# Alert_Button.net
KiCad netlist of a schematic drawn in Altium Designer
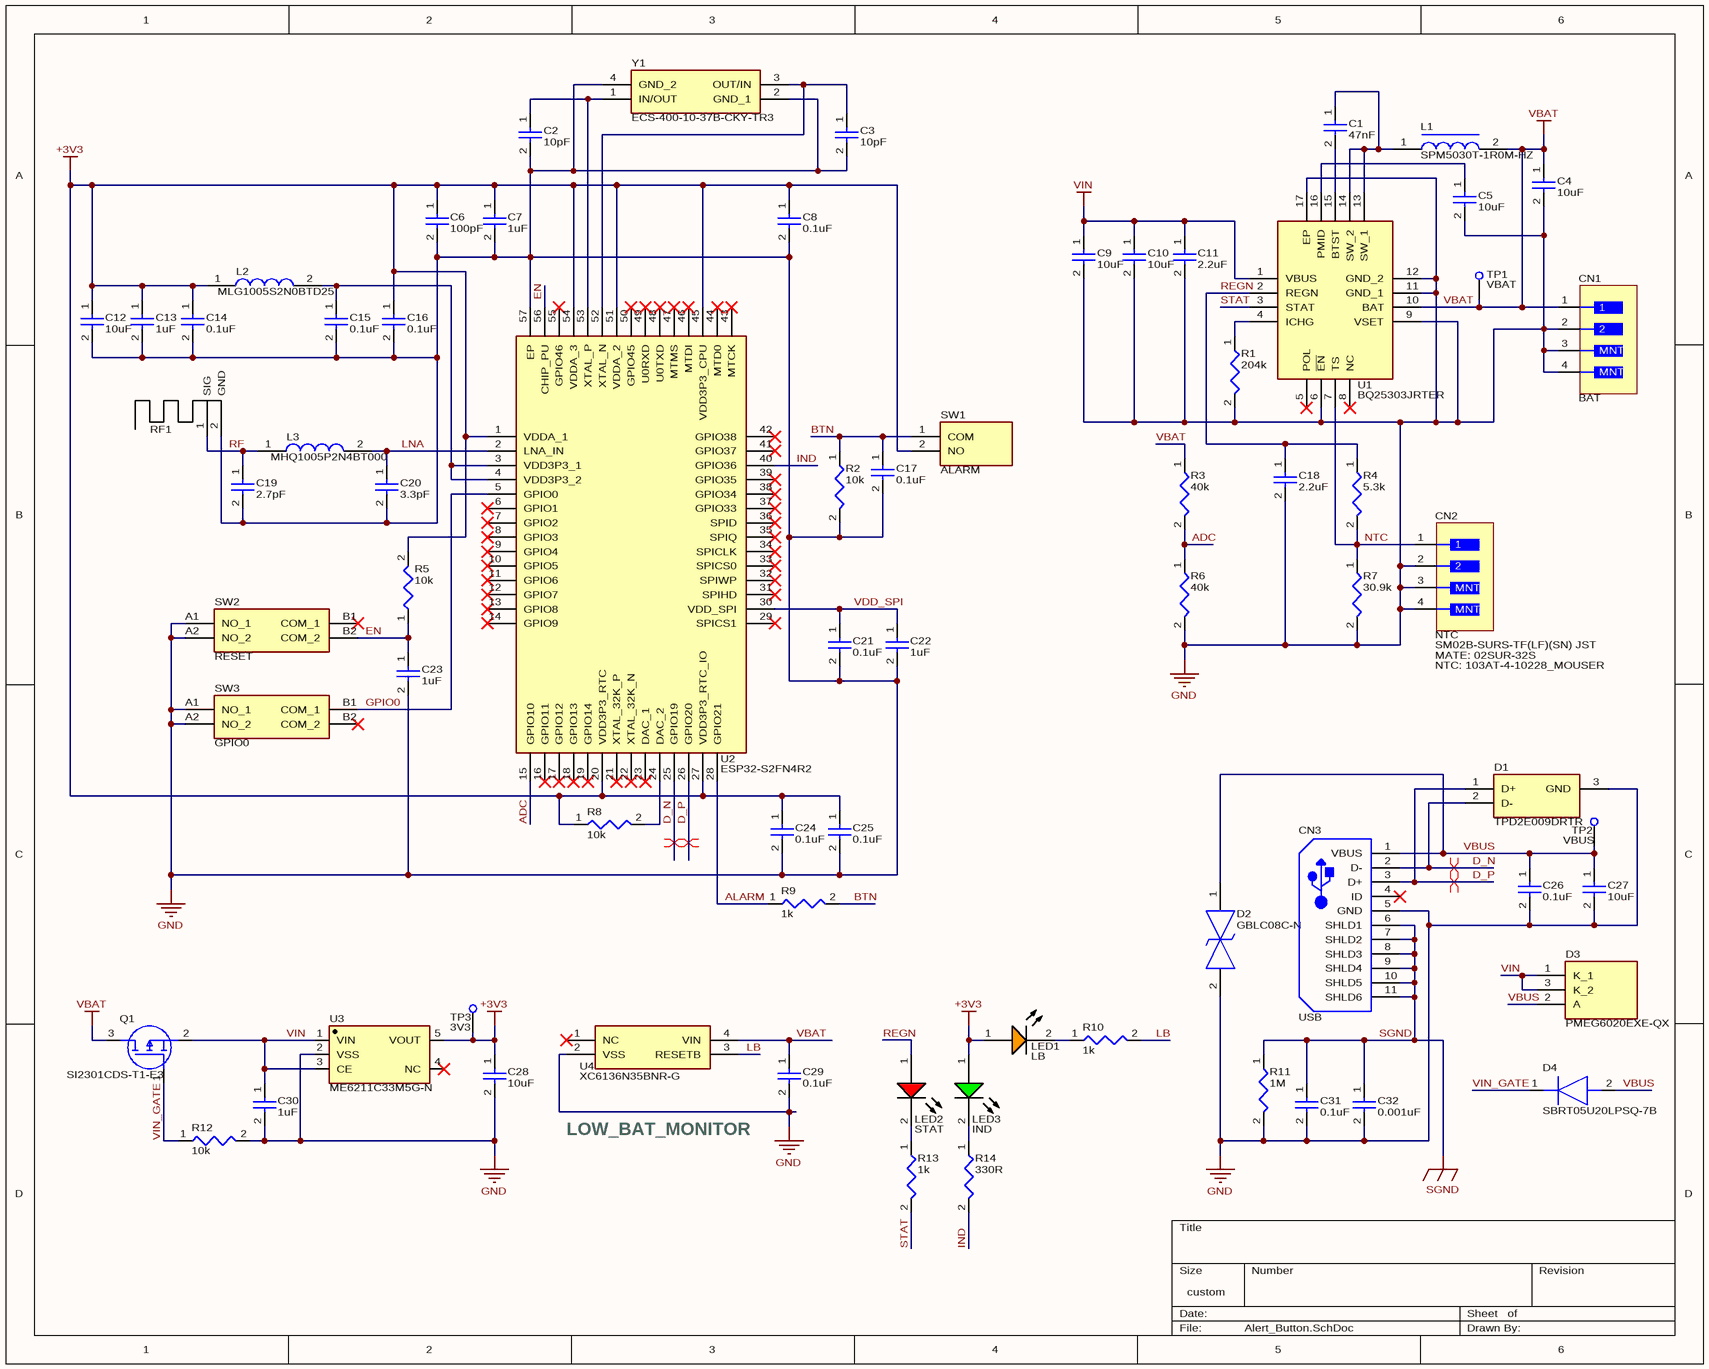
[diagram p0: Alert_Button.SchDoc]

(export (version "E")
  (design (tool "Eeschema 10.0.6"))
  (components
    (comp (ref "C1")
      (value "47nF")
      (footprint "SamacSys:CAPC1005X55N")
      (description "C0402")
      (libsource (lib "SamacSys") (part "C0402"))
    )
    (comp (ref "C2")
      (value "10pF")
      (footprint "SamacSys:CAPC1005X55N")
      (description "C0402")
      (libsource (lib "SamacSys") (part "C0402"))
    )
    (comp (ref "C3")
      (value "10pF")
      (footprint "SamacSys:CAPC1005X55N")
      (description "C0402")
      (libsource (lib "SamacSys") (part "C0402"))
    )
    (comp (ref "C4")
      (value "10uF")
      (footprint "SamacSys:CAPC1608X90N")
      (description "C0603")
      (libsource (lib "SamacSys") (part "C0603"))
    )
    (comp (ref "C5")
      (value "10uF")
      (footprint "SamacSys:CAPC1608X90N")
      (description "C0603")
      (libsource (lib "SamacSys") (part "C0603"))
    )
    (comp (ref "C6")
      (value "100pF")
      (footprint "SamacSys:CAPC1005X55N")
      (description "C0402")
      (libsource (lib "SamacSys") (part "C0402"))
    )
    (comp (ref "C7")
      (value "1uF")
      (footprint "SamacSys:CAPC1005X55N")
      (description "C0402")
      (libsource (lib "SamacSys") (part "C0402"))
    )
    (comp (ref "C8")
      (value "0.1uF")
      (footprint "SamacSys:CAPC1005X55N")
      (description "C0402")
      (libsource (lib "SamacSys") (part "C0402"))
    )
    (comp (ref "C9")
      (value "10uF")
      (footprint "SamacSys:CAPC1608X90N")
      (description "C0603")
      (libsource (lib "SamacSys") (part "C0603"))
    )
    (comp (ref "C10")
      (value "10uF")
      (footprint "SamacSys:CAPC1608X90N")
      (description "C0603")
      (libsource (lib "SamacSys") (part "C0603"))
    )
    (comp (ref "C11")
      (value "2.2uF")
      (footprint "SamacSys:CAPC1005X55N")
      (description "C0402")
      (libsource (lib "SamacSys") (part "C0402"))
    )
    (comp (ref "C12")
      (value "10uF")
      (footprint "SamacSys:CAPC2012X140N")
      (description "C0805")
      (libsource (lib "SamacSys") (part "C0805"))
    )
    (comp (ref "C13")
      (value "1uF")
      (footprint "SamacSys:CAPC1005X55N")
      (description "C0402")
      (libsource (lib "SamacSys") (part "C0402"))
    )
    (comp (ref "C14")
      (value "0.1uF")
      (footprint "SamacSys:CAPC1005X55N")
      (description "C0402")
      (libsource (lib "SamacSys") (part "C0402"))
    )
    (comp (ref "C15")
      (value "0.1uF")
      (footprint "SamacSys:CAPC1005X55N")
      (description "C0402")
      (libsource (lib "SamacSys") (part "C0402"))
    )
    (comp (ref "C16")
      (value "0.1uF")
      (footprint "SamacSys:CAPC1005X55N")
      (description "C0402")
      (libsource (lib "SamacSys") (part "C0402"))
    )
    (comp (ref "C17")
      (value "0.1uF")
      (footprint "SamacSys:CAPC1005X55N")
      (description "C0402")
      (libsource (lib "SamacSys") (part "C0402"))
    )
    (comp (ref "C18")
      (value "2.2uF")
      (footprint "SamacSys:CAPC1005X55N")
      (description "C0402")
      (libsource (lib "SamacSys") (part "C0402"))
    )
    (comp (ref "C19")
      (value "2.7pF")
      (footprint "SamacSys:CAPC1005X56N")
      (description "C0402")
      (fields
        (field (name "MANUFACTURER_PART_NUMBER") "04023U2R7BAT2A")
        (field (name "MOUSER PART NUMBER") "581-04023U2.7B")
      )
      (libsource (lib "SamacSys") (part "04023U2R7BAT2A"))
    )
    (comp (ref "C20")
      (value "3.3pF")
      (footprint "SamacSys:CAPC1005X56N")
      (description "C0402")
      (fields (field (name "MANUFACTURER_PART_NUMBER") "04023A3R3CAT2A"))
      (libsource (lib "SamacSys") (part "04023A3R3CAT2A"))
    )
    (comp (ref "C21")
      (value "0.1uF")
      (footprint "SamacSys:CAPC1005X55N")
      (description "C0402")
      (libsource (lib "SamacSys") (part "C0402"))
    )
    (comp (ref "C22")
      (value "1uF")
      (footprint "SamacSys:CAPC1005X55N")
      (description "C0402")
      (libsource (lib "SamacSys") (part "C0402"))
    )
    (comp (ref "C23")
      (value "1uF")
      (footprint "SamacSys:CAPC1005X55N")
      (description "C0402")
      (libsource (lib "SamacSys") (part "C0402"))
    )
    (comp (ref "C24")
      (value "0.1uF")
      (footprint "SamacSys:CAPC1005X55N")
      (description "C0402")
      (libsource (lib "SamacSys") (part "C0402"))
    )
    (comp (ref "C25")
      (value "0.1uF")
      (footprint "SamacSys:CAPC1005X55N")
      (description "C0402")
      (libsource (lib "SamacSys") (part "C0402"))
    )
    (comp (ref "C26")
      (value "0.1uF")
      (footprint "SamacSys:CAPC1005X55N")
      (description "C0402")
      (libsource (lib "SamacSys") (part "C0402"))
    )
    (comp (ref "C27")
      (value "10uF")
      (footprint "SamacSys:CAPC1608X90N")
      (description "C0603")
      (libsource (lib "SamacSys") (part "C0603"))
    )
    (comp (ref "C28")
      (value "10uF")
      (footprint "SamacSys:CAPC1608X90N")
      (description "C0603")
      (libsource (lib "SamacSys") (part "C0603"))
    )
    (comp (ref "C29")
      (value "0.1uF")
      (footprint "SamacSys:CAPC1005X55N")
      (description "C0402")
      (libsource (lib "") (part "C0402_1"))
    )
    (comp (ref "C30")
      (value "1uF")
      (footprint "SamacSys:CAPC1005X55N")
      (description "C0402")
      (libsource (lib "SamacSys") (part "C0402"))
    )
    (comp (ref "C31")
      (value "0.1uF")
      (footprint "SamacSys:CAPC1005X55N")
      (description "C0402")
      (libsource (lib "SamacSys") (part "C0402"))
    )
    (comp (ref "C32")
      (value "0.001uF")
      (footprint "SamacSys:CAPC1005X55N")
      (description "C0402")
      (libsource (lib "SamacSys") (part "C0402"))
    )
    (comp (ref "CN1")
      (value "BAT")
      (footprint "SM02B-SURS-TF(LF)(SN)")
      (description "Connector")
      (fields
        (field (name "MANUFACTURER_PART_NUMBER") "SM02B-SURS-TF(LF)(SN)")
        (field (name "MOUSER PART NUMBER") "306-SM02B-SURS-TF(LF)(SN)")
      )
      (libsource (lib "Schlib1") (part "SM02B-SURS-TF(LF)(SN)"))
    )
    (comp (ref "CN2")
      (value "NTC")
      (footprint "SM02B-SURS-TF(LF)(SN)")
      (description "Connector")
      (fields
        (field (name "MANUFACTURER_PART_NUMBER") "SM02B-SURS-TF(LF)(SN)")
        (field (name "MOUSER PART NUMBER") "306-SM02B-SURS-TF(LF)(SN)")
      )
      (libsource (lib "Schlib1") (part "SM02B-SURS-TF(LF)(SN)"))
    )
    (comp (ref "CN3")
      (value "USB")
      (footprint "105017-0001")
      (description "Micro USB Connector")
      (fields
        (field (name "MANUFACTURER_PART_NUMBER") "105017-0001")
        (field (name "MOUSER PART NUMBER") "538-105017-0001")
      )
      (libsource (lib "SamacSys") (part "105017-0001"))
    )
    (comp (ref "D1")
      (value "TPD2E009DRTR")
      (footprint "SamacSys:SOTFL35P100X50-3N")
      (description "Integrated Circuit")
      (fields (field (name "MOUSER PART NUMBER") "595-TPD2E009DRTR"))
      (libsource (lib "SamacSys") (part "TPD2E009DRTR"))
    )
    (comp (ref "D2")
      (value "GBLC08C-N")
      (footprint "SOD-323_L1.8-W1.3-LS2.5-BI")
      (description "ESD DIODE-BI_LCSC#C314256")
      (libsource (lib "Schlib1") (part "GBLC08C-N"))
    )
    (comp (ref "D3")
      (value "PMEG6020EXE-QX")
      (footprint "SamacSys:PMEG6020EXEQX")
      (description "Schottky Diode")
      (libsource (lib "SamacSys") (part "PMEG6020EXE-QX"))
    )
    (comp (ref "D4")
      (value "SBRT05U20LPSQ-7B")
      (footprint "SamacSys:SBRT05U20LPSQ7B")
      (description "Diode")
      (fields (field (name "MOUSER PART NUMBER") "621-SBRT05U20LPSQ-7B"))
      (libsource (lib "SamacSys") (part "SBRT05U20LPSQ-7B"))
    )
    (comp (ref "L1")
      (value "SPM5030T-1R0M-HZ")
      (footprint "SamacSys:SPM5030")
      (description "Inductor (FeSi Core)")
      (fields (field (name "MOUSER PART NUMBER") "810-SPM5030T-1R0M-HZ"))
      (libsource (lib "SamacSys") (part "SPM5030T-1R0M-HZ"))
    )
    (comp (ref "L2")
      (value "MLG1005S2N0BTD25")
      (footprint "SamacSys:MLG1005")
      (description "Inductor")
      (fields (field (name "MOUSER PART NUMBER") "810-MLG1005S2N0BTD25"))
      (libsource (lib "SamacSys") (part "MLG1005S2N0BTD25"))
    )
    (comp (ref "L3")
      (value "MHQ1005P2N4BT000")
      (footprint "SamacSys:MHQ1005")
      (description "Inductor")
      (libsource (lib "SamacSys") (part "MHQ1005P2N4BT000"))
    )
    (comp (ref "LED1")
      (value "LB")
      (footprint "SM0402OC")
      (description "LED ORANGE")
      (fields
        (field (name "MANUFACTURER_PART_NUMBER") "SM0402OC")
        (field (name "MOUSER PART NUMBER") "749-SM0402OC")
      )
      (libsource (lib "SamacSys") (part "SM0402OC"))
    )
    (comp (ref "LED2")
      (value "STAT")
      (footprint "SamacSys:SM0402RC")
      (description "LED RED")
      (fields
        (field (name "MANUFACTURER_PART_NUMBER") "SM0402RC")
        (field (name "MOUSER PART NUMBER") "749-SM0402RC")
      )
      (libsource (lib "SamacSys") (part "SM0402RC"))
    )
    (comp (ref "LED3")
      (value "IND")
      (footprint "SamacSys:SM0402GC")
      (description "LED GREEN")
      (fields
        (field (name "MANUFACTURER_PART_NUMBER") "SM0402GC")
        (field (name "MOUSER PART NUMBER") "749-SM0402GC")
      )
      (libsource (lib "SamacSys") (part "SM0402GC"))
    )
    (comp (ref "Q1")
      (value "SI2301CDS-T1-E3")
      (footprint "SamacSys:SOT95P237X112-3N")
      (description "MOSFET (P-Channel)")
      (fields (field (name "MOUSER PART NUMBER") "781-SI2301CDS-E3"))
      (libsource (lib "SamacSys") (part "SI2301CDS-T1-E3"))
    )
    (comp (ref "R1")
      (value "204k")
      (footprint "SamacSys:ERA2AED122X")
      (description "R0402")
      (libsource (lib "SamacSys") (part "R0402"))
    )
    (comp (ref "R2")
      (value "10k")
      (footprint "SamacSys:ERA2AED122X")
      (description "R0402")
      (libsource (lib "SamacSys") (part "R0402"))
    )
    (comp (ref "R3")
      (value "40k")
      (footprint "SamacSys:ERA2AED122X")
      (description "R0402")
      (libsource (lib "SamacSys") (part "R0402"))
    )
    (comp (ref "R4")
      (value "5.3k")
      (footprint "SamacSys:ERA2AED122X")
      (description "R0402")
      (libsource (lib "SamacSys") (part "R0402"))
    )
    (comp (ref "R5")
      (value "10k")
      (footprint "SamacSys:ERA2AED122X")
      (description "R0402")
      (libsource (lib "SamacSys") (part "R0402"))
    )
    (comp (ref "R6")
      (value "40k")
      (footprint "SamacSys:ERA2AED122X")
      (description "R0402")
      (libsource (lib "SamacSys") (part "R0402"))
    )
    (comp (ref "R7")
      (value "30.9k")
      (footprint "SamacSys:ERA2AED122X")
      (description "R0402")
      (libsource (lib "SamacSys") (part "R0402"))
    )
    (comp (ref "R8")
      (value "10k")
      (footprint "SamacSys:ERA2AED122X")
      (description "R0402")
      (libsource (lib "SamacSys") (part "R0402"))
    )
    (comp (ref "R9")
      (value "1k")
      (footprint "SamacSys:ERA2AED122X")
      (description "R0402")
      (libsource (lib "SamacSys") (part "R0402"))
    )
    (comp (ref "R10")
      (value "1k")
      (footprint "SamacSys:ERA2AED122X")
      (description "R0402")
      (libsource (lib "SamacSys") (part "R0402"))
    )
    (comp (ref "R11")
      (value "1M")
      (footprint "SamacSys:ERA2AED122X")
      (description "R0402")
      (libsource (lib "SamacSys") (part "R0402"))
    )
    (comp (ref "R12")
      (value "10k")
      (footprint "SamacSys:ERA2AED122X")
      (description "R0402")
      (libsource (lib "SamacSys") (part "R0402"))
    )
    (comp (ref "R13")
      (value "1k")
      (footprint "SamacSys:ERA2AED122X")
      (description "R0402")
      (libsource (lib "SamacSys") (part "R0402"))
    )
    (comp (ref "R14")
      (value "330R")
      (footprint "SamacSys:ERA2AED122X")
      (description "R0402")
      (libsource (lib "SamacSys") (part "R0402"))
    )
    (comp (ref "RF1") (value "Antenna") (footprint "SWRA117D") (libsource (lib "Schlib1") (part "Antenna")))
    (comp (ref "SW1")
      (value "ALARM")
      (footprint "SamacSys:TS1088R02026")
      (description "Switch")
      (fields (field (name "MANUFACTURER_PART_NUMBER") "TS-1088R-02026"))
      (libsource (lib "SamacSys") (part "TS-1088R-02026"))
    )
    (comp (ref "SW2")
      (value "RESET")
      (footprint "SamacSys:EVPBB0AAB000")
      (description "Switch")
      (fields
        (field (name "MANUFACTURER_PART_NUMBER") "EVP-BB0AAB000")
        (field (name "MOUSER PART NUMBER") "667-EVP-BB0AAB000")
      )
      (libsource (lib "SamacSys") (part "EVP-BB0AAB000"))
    )
    (comp (ref "SW3")
      (value "GPIO0")
      (footprint "SamacSys:EVPBB0AAB000")
      (description "Switch")
      (fields
        (field (name "MANUFACTURER_PART_NUMBER") "EVP-BB0AAB000")
        (field (name "MOUSER PART NUMBER") "667-EVP-BB0AAB000")
      )
      (libsource (lib "SamacSys") (part "EVP-BB0AAB000"))
    )
    (comp (ref "TP1")
      (value "VBAT")
      (footprint "TP")
      (description "TestPoint")
      (libsource (lib "Schlib1") (part "TestPoint"))
    )
    (comp (ref "TP2")
      (value "VBUS")
      (footprint "TP")
      (description "TestPoint")
      (libsource (lib "Schlib1") (part "TestPoint"))
    )
    (comp (ref "TP3")
      (value "3V3")
      (footprint "TP")
      (description "TestPoint")
      (libsource (lib "Schlib1") (part "TestPoint"))
    )
    (comp (ref "U1")
      (value "BQ25303JRTER")
      (footprint "SamacSys:QFN50P300X300X80-17N-D")
      (description "Integrated Circuit")
      (fields (field (name "MOUSER PART NUMBER") "595-BQ25303JRTER"))
      (libsource (lib "*") (part "BQ25303JRTER"))
    )
    (comp (ref "U2")
      (value "ESP32-S2FN4R2")
      (footprint "SamacSys:QFN40P700X700X90-57N-D")
      (description "Integrated Circuit")
      (fields (field (name "MOUSER PART NUMBER") "356-ESP32-S2FN4R2"))
      (libsource (lib "SamacSys") (part "ESP32-S2FN4R2"))
    )
    (comp (ref "U3")
      (value "ME6211C33M5G-N")
      (footprint "SOT95P270X145-5N")
      (description "LCSC +3.3V LDO 500mA VDIF=120mV@100mA")
      (libsource (lib "Schlib1") (part "ME6211C33M5G-N"))
    )
    (comp (ref "U4")
      (value "XC6136N35BNR-G")
      (footprint "SamacSys:XC6136C12ANRG")
      (description "Integrated Circuit")
      (fields (field (name "MOUSER PART NUMBER") "865-XC6136N35BNR-G"))
      (libsource (lib "SamacSys") (part "XC6136N35BNR-G"))
    )
    (comp (ref "Y1")
      (value "ECS-400-10-37B-CKY-TR3")
      (footprint "SamacSys:ECS4001037BCKYTR3")
      (description "Crystal or Oscillator")
      (fields (field (name "MOUSER PART NUMBER") "520-EC4001037BCKYTR3"))
      (libsource (lib "SamacSys") (part "ECS-400-10-37B-CKY-TR3"))
    )
  )
  (nets
    (net (code "1") (name "+3V3") (class "Default")
      (node (ref "C12") (pin "1") (pinfunction "1_1") (pintype "passive"))
      (node (ref "C13") (pin "1") (pinfunction "1_1") (pintype "passive"))
      (node (ref "C14") (pin "1") (pinfunction "1_1") (pintype "passive"))
      (node (ref "C16") (pin "1") (pinfunction "1_1") (pintype "passive"))
      (node (ref "C24") (pin "1") (pinfunction "1_1") (pintype "passive"))
      (node (ref "C25") (pin "1") (pinfunction "1_1") (pintype "passive"))
      (node (ref "C28") (pin "1") (pinfunction "1_1") (pintype "passive"))
      (node (ref "C6") (pin "1") (pinfunction "1_1") (pintype "passive"))
      (node (ref "C7") (pin "1") (pinfunction "1_1") (pintype "passive"))
      (node (ref "C8") (pin "1") (pinfunction "1_1") (pintype "passive"))
      (node (ref "L2") (pin "1") (pinfunction "1_1") (pintype "passive"))
      (node (ref "LED1") (pin "1") (pinfunction "A_1") (pintype "passive"))
      (node (ref "LED3") (pin "1") (pinfunction "A_1") (pintype "passive"))
      (node (ref "R5") (pin "2") (pinfunction "2_2") (pintype "passive"))
      (node (ref "R8") (pin "1") (pinfunction "1_1") (pintype "passive"))
      (node (ref "SW1") (pin "2") (pinfunction "NO_2") (pintype "passive"))
      (node (ref "TP3") (pin "1") (pinfunction "1_1") (pintype "passive"))
      (node (ref "U2") (pin "1") (pinfunction "VDDA_1_1") (pintype "passive"))
      (node (ref "U2") (pin "20") (pinfunction "VDD3P3_RTC_20") (pintype "passive"))
      (node (ref "U2") (pin "27") (pinfunction "VDD3P3_RTC_IO_27") (pintype "passive"))
      (node (ref "U2") (pin "45") (pinfunction "VDD3P3_CPU_45") (pintype "passive"))
      (node (ref "U2") (pin "51") (pinfunction "VDDA_2_51") (pintype "passive"))
      (node (ref "U2") (pin "54") (pinfunction "VDDA_3_54") (pintype "passive"))
      (node (ref "U3") (pin "5") (pinfunction "VOUT_5") (pintype "passive"))
    )
    (net (code "2") (name "/ADC") (class "Default")
      (node (ref "R3") (pin "2") (pinfunction "2_2") (pintype "passive"))
      (node (ref "R6") (pin "1") (pinfunction "1_1") (pintype "passive"))
      (node (ref "U2") (pin "15") (pinfunction "GPIO10_15") (pintype "passive"))
    )
    (net (code "3") (name "/ALARM") (class "Default")
      (node (ref "R9") (pin "1") (pinfunction "1_1") (pintype "passive"))
      (node (ref "U2") (pin "28") (pinfunction "GPIO21_28") (pintype "passive"))
    )
    (net (code "4") (name "/BTN") (class "Default")
      (node (ref "C17") (pin "1") (pinfunction "1_1") (pintype "passive"))
      (node (ref "R2") (pin "1") (pinfunction "1_1") (pintype "passive"))
      (node (ref "R9") (pin "2") (pinfunction "2_2") (pintype "passive"))
      (node (ref "SW1") (pin "1") (pinfunction "COM_1") (pintype "passive"))
    )
    (net (code "5") (name "/D_N") (class "Default")
      (node (ref "CN3") (pin "2") (pinfunction "D-_2") (pintype "passive"))
      (node (ref "D1") (pin "2") (pinfunction "D-_2") (pintype "passive"))
      (node (ref "U2") (pin "25") (pinfunction "GPIO19_25") (pintype "passive"))
    )
    (net (code "6") (name "/D_P") (class "Default")
      (node (ref "CN3") (pin "3") (pinfunction "D+_3") (pintype "passive"))
      (node (ref "D1") (pin "1") (pinfunction "D+_1") (pintype "passive"))
      (node (ref "U2") (pin "26") (pinfunction "GPIO20_26") (pintype "passive"))
    )
    (net (code "7") (name "/EN") (class "Default")
      (node (ref "C23") (pin "1") (pinfunction "1_1") (pintype "passive"))
      (node (ref "R5") (pin "1") (pinfunction "1_1") (pintype "passive"))
      (node (ref "SW2") (pin "B2") (pinfunction "COM_2_B2") (pintype "passive"))
      (node (ref "U2") (pin "56") (pinfunction "CHIP_PU_56") (pintype "passive"))
    )
    (net (code "8") (name "/GPIO0") (class "Default")
      (node (ref "SW3") (pin "B1") (pinfunction "COM_1_B1") (pintype "passive"))
      (node (ref "U2") (pin "5") (pinfunction "GPIO0_5") (pintype "passive"))
    )
    (net (code "9") (name "/IND") (class "Default")
      (node (ref "R14") (pin "2") (pinfunction "2_2") (pintype "passive"))
      (node (ref "U2") (pin "40") (pinfunction "GPIO36_40") (pintype "passive"))
    )
    (net (code "10") (name "/LB") (class "Default")
      (node (ref "R10") (pin "2") (pinfunction "2_2") (pintype "passive"))
      (node (ref "U4") (pin "3") (pinfunction "RESETB_3") (pintype "passive"))
    )
    (net (code "11") (name "/LNA") (class "Default")
      (node (ref "C20") (pin "1") (pinfunction "1_1") (pintype "passive"))
      (node (ref "L3") (pin "2") (pinfunction "2_2") (pintype "passive"))
      (node (ref "U2") (pin "2") (pinfunction "LNA_IN_2") (pintype "passive"))
    )
    (net (code "12") (name "/NTC") (class "Default")
      (node (ref "CN2") (pin "1") (pinfunction "1_1") (pintype "passive"))
      (node (ref "R4") (pin "2") (pinfunction "2_2") (pintype "passive"))
      (node (ref "R7") (pin "1") (pinfunction "1_1") (pintype "passive"))
      (node (ref "U1") (pin "7") (pinfunction "TS_7") (pintype "passive"))
    )
    (net (code "13") (name "/REGN") (class "Default")
      (node (ref "C18") (pin "1") (pinfunction "1_1") (pintype "passive"))
      (node (ref "LED2") (pin "1") (pinfunction "A_1") (pintype "passive"))
      (node (ref "R4") (pin "1") (pinfunction "1_1") (pintype "passive"))
      (node (ref "U1") (pin "2") (pinfunction "REGN_2") (pintype "passive"))
    )
    (net (code "14") (name "/RF") (class "Default")
      (node (ref "C19") (pin "1") (pinfunction "1_1") (pintype "passive"))
      (node (ref "L3") (pin "1") (pinfunction "1_1") (pintype "passive"))
      (node (ref "RF1") (pin "1") (pinfunction "SIG_1") (pintype "passive"))
    )
    (net (code "15") (name "/STAT") (class "Default")
      (node (ref "R13") (pin "2") (pinfunction "2_2") (pintype "passive"))
      (node (ref "U1") (pin "3") (pinfunction "STAT_3") (pintype "passive"))
    )
    (net (code "16") (name "/VBUS") (class "Default")
      (node (ref "C26") (pin "1") (pinfunction "1_1") (pintype "passive"))
      (node (ref "C27") (pin "1") (pinfunction "1_1") (pintype "passive"))
      (node (ref "CN3") (pin "1") (pinfunction "VBUS_1") (pintype "passive"))
      (node (ref "D2") (pin "1") (pinfunction "1_1") (pintype "passive"))
      (node (ref "D3") (pin "2") (pinfunction "A_2") (pintype "passive"))
      (node (ref "D4") (pin "2") (pinfunction "A_2") (pintype "passive"))
      (node (ref "TP2") (pin "1") (pinfunction "1_1") (pintype "passive"))
    )
    (net (code "17") (name "/VDD_SPI") (class "Default")
      (node (ref "C21") (pin "1") (pinfunction "1_1") (pintype "passive"))
      (node (ref "C22") (pin "1") (pinfunction "1_1") (pintype "passive"))
      (node (ref "U2") (pin "30") (pinfunction "VDD_SPI_30") (pintype "passive"))
    )
    (net (code "18") (name "/VIN_GATE") (class "Default")
      (node (ref "D4") (pin "1") (pinfunction "K_1") (pintype "passive"))
      (node (ref "Q1") (pin "1") (pinfunction "G_1") (pintype "passive"))
      (node (ref "R12") (pin "1") (pinfunction "1_1") (pintype "passive"))
    )
    (net (code "19") (name "GND") (class "Default")
      (node (ref "C10") (pin "2") (pinfunction "2_2") (pintype "passive"))
      (node (ref "C11") (pin "2") (pinfunction "2_2") (pintype "passive"))
      (node (ref "C12") (pin "2") (pinfunction "2_2") (pintype "passive"))
      (node (ref "C13") (pin "2") (pinfunction "2_2") (pintype "passive"))
      (node (ref "C14") (pin "2") (pinfunction "2_2") (pintype "passive"))
      (node (ref "C15") (pin "2") (pinfunction "2_2") (pintype "passive"))
      (node (ref "C16") (pin "2") (pinfunction "2_2") (pintype "passive"))
      (node (ref "C17") (pin "2") (pinfunction "2_2") (pintype "passive"))
      (node (ref "C18") (pin "2") (pinfunction "2_2") (pintype "passive"))
      (node (ref "C19") (pin "2") (pinfunction "2_2") (pintype "passive"))
      (node (ref "C2") (pin "2") (pinfunction "2_2") (pintype "passive"))
      (node (ref "C20") (pin "2") (pinfunction "2_2") (pintype "passive"))
      (node (ref "C21") (pin "2") (pinfunction "2_2") (pintype "passive"))
      (node (ref "C22") (pin "2") (pinfunction "2_2") (pintype "passive"))
      (node (ref "C23") (pin "2") (pinfunction "2_2") (pintype "passive"))
      (node (ref "C24") (pin "2") (pinfunction "2_2") (pintype "passive"))
      (node (ref "C25") (pin "2") (pinfunction "2_2") (pintype "passive"))
      (node (ref "C26") (pin "2") (pinfunction "2_2") (pintype "passive"))
      (node (ref "C27") (pin "2") (pinfunction "2_2") (pintype "passive"))
      (node (ref "C28") (pin "2") (pinfunction "2_2") (pintype "passive"))
      (node (ref "C29") (pin "2") (pinfunction "2_2") (pintype "passive"))
      (node (ref "C3") (pin "2") (pinfunction "2_2") (pintype "passive"))
      (node (ref "C30") (pin "2") (pinfunction "2_2") (pintype "passive"))
      (node (ref "C31") (pin "2") (pinfunction "2_2") (pintype "passive"))
      (node (ref "C32") (pin "2") (pinfunction "2_2") (pintype "passive"))
      (node (ref "C4") (pin "2") (pinfunction "2_2") (pintype "passive"))
      (node (ref "C5") (pin "2") (pinfunction "2_2") (pintype "passive"))
      (node (ref "C6") (pin "2") (pinfunction "2_2") (pintype "passive"))
      (node (ref "C7") (pin "2") (pinfunction "2_2") (pintype "passive"))
      (node (ref "C8") (pin "2") (pinfunction "2_2") (pintype "passive"))
      (node (ref "C9") (pin "2") (pinfunction "2_2") (pintype "passive"))
      (node (ref "CN1") (pin "2") (pinfunction "2_2") (pintype "passive"))
      (node (ref "CN1") (pin "3") (pinfunction "MNT_3") (pintype "passive"))
      (node (ref "CN1") (pin "4") (pinfunction "MNT_4") (pintype "passive"))
      (node (ref "CN2") (pin "2") (pinfunction "2_2") (pintype "passive"))
      (node (ref "CN2") (pin "3") (pinfunction "MNT_3") (pintype "passive"))
      (node (ref "CN2") (pin "4") (pinfunction "MNT_4") (pintype "passive"))
      (node (ref "CN3") (pin "5") (pinfunction "GND_5") (pintype "passive"))
      (node (ref "D1") (pin "3") (pinfunction "GND_3") (pintype "passive"))
      (node (ref "D2") (pin "2") (pinfunction "2_2") (pintype "passive"))
      (node (ref "R1") (pin "2") (pinfunction "2_2") (pintype "passive"))
      (node (ref "R11") (pin "2") (pinfunction "2_2") (pintype "passive"))
      (node (ref "R12") (pin "2") (pinfunction "2_2") (pintype "passive"))
      (node (ref "R2") (pin "2") (pinfunction "2_2") (pintype "passive"))
      (node (ref "R6") (pin "2") (pinfunction "2_2") (pintype "passive"))
      (node (ref "R7") (pin "2") (pinfunction "2_2") (pintype "passive"))
      (node (ref "RF1") (pin "2") (pinfunction "GND_2") (pintype "passive"))
      (node (ref "SW2") (pin "A1") (pinfunction "NO_1_A1") (pintype "passive"))
      (node (ref "SW2") (pin "A2") (pinfunction "NO_2_A2") (pintype "passive"))
      (node (ref "SW3") (pin "A1") (pinfunction "NO_1_A1") (pintype "passive"))
      (node (ref "SW3") (pin "A2") (pinfunction "NO_2_A2") (pintype "passive"))
      (node (ref "U1") (pin "11") (pinfunction "GND_1_11") (pintype "passive"))
      (node (ref "U1") (pin "12") (pinfunction "GND_2_12") (pintype "passive"))
      (node (ref "U1") (pin "17") (pinfunction "EP_17") (pintype "passive"))
      (node (ref "U1") (pin "6") (pinfunction "~{EN}_6") (pintype "passive"))
      (node (ref "U1") (pin "9") (pinfunction "VSET_9") (pintype "passive"))
      (node (ref "U2") (pin "57") (pinfunction "EP_57") (pintype "passive"))
      (node (ref "U3") (pin "2") (pinfunction "VSS_2") (pintype "passive"))
      (node (ref "U4") (pin "2") (pinfunction "VSS_2") (pintype "passive"))
      (node (ref "Y1") (pin "2") (pinfunction "GND_1_2") (pintype "passive"))
      (node (ref "Y1") (pin "4") (pinfunction "GND_2_4") (pintype "passive"))
    )
    (net (code "20") (name "Net-(LED1-K)") (class "Default")
      (node (ref "LED1") (pin "2") (pinfunction "K_2") (pintype "passive"))
      (node (ref "R10") (pin "1") (pinfunction "1_1") (pintype "passive"))
    )
    (net (code "21") (name "Net-(LED2-K)") (class "Default")
      (node (ref "LED2") (pin "2") (pinfunction "K_2") (pintype "passive"))
      (node (ref "R13") (pin "1") (pinfunction "1_1") (pintype "passive"))
    )
    (net (code "22") (name "Net-(LED3-K)") (class "Default")
      (node (ref "LED3") (pin "2") (pinfunction "K_2") (pintype "passive"))
      (node (ref "R14") (pin "1") (pinfunction "1_1") (pintype "passive"))
    )
    (net (code "23") (name "Net-(U1-BTST)") (class "Default")
      (node (ref "C1") (pin "2") (pinfunction "2_2") (pintype "passive"))
      (node (ref "U1") (pin "15") (pinfunction "BTST_15") (pintype "passive"))
    )
    (net (code "24") (name "Net-(U1-ICHG)") (class "Default")
      (node (ref "R1") (pin "1") (pinfunction "1_1") (pintype "passive"))
      (node (ref "U1") (pin "4") (pinfunction "ICHG_4") (pintype "passive"))
    )
    (net (code "25") (name "Net-(U1-PMID)") (class "Default")
      (node (ref "C5") (pin "1") (pinfunction "1_1") (pintype "passive"))
      (node (ref "U1") (pin "16") (pinfunction "PMID_16") (pintype "passive"))
    )
    (net (code "26") (name "Net-(U1-SW_1)") (class "Default")
      (node (ref "C1") (pin "1") (pinfunction "1_1") (pintype "passive"))
      (node (ref "L1") (pin "1") (pinfunction "1_1") (pintype "passive"))
      (node (ref "U1") (pin "13") (pinfunction "SW_1_13") (pintype "passive"))
      (node (ref "U1") (pin "14") (pinfunction "SW_2_14") (pintype "passive"))
    )
    (net (code "27") (name "Net-(U2-DAC_2)") (class "Default")
      (node (ref "R8") (pin "2") (pinfunction "2_2") (pintype "passive"))
      (node (ref "U2") (pin "24") (pinfunction "DAC_2_24") (pintype "passive"))
    )
    (net (code "28") (name "Net-(U2-VDD3P3_1)") (class "Default")
      (node (ref "C15") (pin "1") (pinfunction "1_1") (pintype "passive"))
      (node (ref "L2") (pin "2") (pinfunction "2_2") (pintype "passive"))
      (node (ref "U2") (pin "3") (pinfunction "VDD3P3_1_3") (pintype "passive"))
      (node (ref "U2") (pin "4") (pinfunction "VDD3P3_2_4") (pintype "passive"))
    )
    (net (code "29") (name "Net-(U2-XTAL_N)") (class "Default")
      (node (ref "C3") (pin "1") (pinfunction "1_1") (pintype "passive"))
      (node (ref "U2") (pin "52") (pinfunction "XTAL_N_52") (pintype "passive"))
      (node (ref "Y1") (pin "3") (pinfunction "OUT/IN_3") (pintype "passive"))
    )
    (net (code "30") (name "Net-(U2-XTAL_P)") (class "Default")
      (node (ref "C2") (pin "1") (pinfunction "1_1") (pintype "passive"))
      (node (ref "U2") (pin "53") (pinfunction "XTAL_P_53") (pintype "passive"))
      (node (ref "Y1") (pin "1") (pinfunction "IN/OUT_1") (pintype "passive"))
    )
    (net (code "31") (name "SGND") (class "Default")
      (node (ref "C31") (pin "1") (pinfunction "1_1") (pintype "passive"))
      (node (ref "C32") (pin "1") (pinfunction "1_1") (pintype "passive"))
      (node (ref "CN3") (pin "10") (pinfunction "SHLD5_10") (pintype "passive"))
      (node (ref "CN3") (pin "11") (pinfunction "SHLD6_11") (pintype "passive"))
      (node (ref "CN3") (pin "6") (pinfunction "SHLD1_6") (pintype "passive"))
      (node (ref "CN3") (pin "7") (pinfunction "SHLD2_7") (pintype "passive"))
      (node (ref "CN3") (pin "8") (pinfunction "SHLD3_8") (pintype "passive"))
      (node (ref "CN3") (pin "9") (pinfunction "SHLD4_9") (pintype "passive"))
      (node (ref "R11") (pin "1") (pinfunction "1_1") (pintype "passive"))
    )
    (net (code "32") (name "VBAT") (class "Default")
      (node (ref "C29") (pin "1") (pinfunction "1_1") (pintype "passive"))
      (node (ref "C4") (pin "1") (pinfunction "1_1") (pintype "passive"))
      (node (ref "CN1") (pin "1") (pinfunction "1_1") (pintype "passive"))
      (node (ref "L1") (pin "2") (pinfunction "2_2") (pintype "passive"))
      (node (ref "Q1") (pin "3") (pinfunction "D_3") (pintype "passive"))
      (node (ref "R3") (pin "1") (pinfunction "1_1") (pintype "passive"))
      (node (ref "TP1") (pin "1") (pinfunction "1_1") (pintype "passive"))
      (node (ref "U1") (pin "10") (pinfunction "BAT_10") (pintype "passive"))
      (node (ref "U4") (pin "4") (pinfunction "VIN_4") (pintype "passive"))
    )
    (net (code "33") (name "VIN") (class "Default")
      (node (ref "C10") (pin "1") (pinfunction "1_1") (pintype "passive"))
      (node (ref "C11") (pin "1") (pinfunction "1_1") (pintype "passive"))
      (node (ref "C30") (pin "1") (pinfunction "1_1") (pintype "passive"))
      (node (ref "C9") (pin "1") (pinfunction "1_1") (pintype "passive"))
      (node (ref "D3") (pin "1") (pinfunction "K_1_1") (pintype "passive"))
      (node (ref "D3") (pin "3") (pinfunction "K_2_3") (pintype "passive"))
      (node (ref "Q1") (pin "2") (pinfunction "S_2") (pintype "passive"))
      (node (ref "U1") (pin "1") (pinfunction "VBUS_1") (pintype "passive"))
      (node (ref "U3") (pin "1") (pinfunction "VIN_1") (pintype "passive"))
      (node (ref "U3") (pin "3") (pinfunction "CE_3") (pintype "passive"))
    )
    (net (code "34") (name "unconnected-(CN3-ID-Pad4)") (class "Default")
      (node (ref "CN3") (pin "4") (pinfunction "ID_4") (pintype "passive+no_connect"))
    )
    (net (code "35") (name "unconnected-(SW2-COM_1-PadB1)") (class "Default")
      (node (ref "SW2") (pin "B1") (pinfunction "COM_1_B1") (pintype "passive+no_connect"))
    )
    (net (code "36") (name "unconnected-(SW3-COM_2-PadB2)") (class "Default")
      (node (ref "SW3") (pin "B2") (pinfunction "COM_2_B2") (pintype "passive+no_connect"))
    )
    (net (code "37") (name "unconnected-(U1-NC-Pad8)") (class "Default")
      (node (ref "U1") (pin "8") (pinfunction "NC_8") (pintype "passive+no_connect"))
    )
    (net (code "38") (name "unconnected-(U1-POL-Pad5)") (class "Default")
      (node (ref "U1") (pin "5") (pinfunction "POL_5") (pintype "passive+no_connect"))
    )
    (net (code "39") (name "unconnected-(U2-DAC_1-Pad23)") (class "Default")
      (node (ref "U2") (pin "23") (pinfunction "DAC_1_23") (pintype "passive+no_connect"))
    )
    (net (code "40") (name "unconnected-(U2-GPIO1-Pad6)") (class "Default")
      (node (ref "U2") (pin "6") (pinfunction "GPIO1_6") (pintype "passive+no_connect"))
    )
    (net (code "41") (name "unconnected-(U2-GPIO2-Pad7)") (class "Default")
      (node (ref "U2") (pin "7") (pinfunction "GPIO2_7") (pintype "passive+no_connect"))
    )
    (net (code "42") (name "unconnected-(U2-GPIO3-Pad8)") (class "Default")
      (node (ref "U2") (pin "8") (pinfunction "GPIO3_8") (pintype "passive+no_connect"))
    )
    (net (code "43") (name "unconnected-(U2-GPIO4-Pad9)") (class "Default")
      (node (ref "U2") (pin "9") (pinfunction "GPIO4_9") (pintype "passive+no_connect"))
    )
    (net (code "44") (name "unconnected-(U2-GPIO5-Pad10)") (class "Default")
      (node (ref "U2") (pin "10") (pinfunction "GPIO5_10") (pintype "passive+no_connect"))
    )
    (net (code "45") (name "unconnected-(U2-GPIO6-Pad11)") (class "Default")
      (node (ref "U2") (pin "11") (pinfunction "GPIO6_11") (pintype "passive+no_connect"))
    )
    (net (code "46") (name "unconnected-(U2-GPIO7-Pad12)") (class "Default")
      (node (ref "U2") (pin "12") (pinfunction "GPIO7_12") (pintype "passive+no_connect"))
    )
    (net (code "47") (name "unconnected-(U2-GPIO8-Pad13)") (class "Default")
      (node (ref "U2") (pin "13") (pinfunction "GPIO8_13") (pintype "passive+no_connect"))
    )
    (net (code "48") (name "unconnected-(U2-GPIO9-Pad14)") (class "Default")
      (node (ref "U2") (pin "14") (pinfunction "GPIO9_14") (pintype "passive+no_connect"))
    )
    (net (code "49") (name "unconnected-(U2-GPIO11-Pad16)") (class "Default")
      (node (ref "U2") (pin "16") (pinfunction "GPIO11_16") (pintype "passive+no_connect"))
    )
    (net (code "50") (name "unconnected-(U2-GPIO12-Pad17)") (class "Default")
      (node (ref "U2") (pin "17") (pinfunction "GPIO12_17") (pintype "passive+no_connect"))
    )
    (net (code "51") (name "unconnected-(U2-GPIO13-Pad18)") (class "Default")
      (node (ref "U2") (pin "18") (pinfunction "GPIO13_18") (pintype "passive+no_connect"))
    )
    (net (code "52") (name "unconnected-(U2-GPIO14-Pad19)") (class "Default")
      (node (ref "U2") (pin "19") (pinfunction "GPIO14_19") (pintype "passive+no_connect"))
    )
    (net (code "53") (name "unconnected-(U2-GPIO33-Pad37)") (class "Default")
      (node (ref "U2") (pin "37") (pinfunction "GPIO33_37") (pintype "passive+no_connect"))
    )
    (net (code "54") (name "unconnected-(U2-GPIO34-Pad38)") (class "Default")
      (node (ref "U2") (pin "38") (pinfunction "GPIO34_38") (pintype "passive+no_connect"))
    )
    (net (code "55") (name "unconnected-(U2-GPIO35-Pad39)") (class "Default")
      (node (ref "U2") (pin "39") (pinfunction "GPIO35_39") (pintype "passive+no_connect"))
    )
    (net (code "56") (name "unconnected-(U2-GPIO37-Pad41)") (class "Default")
      (node (ref "U2") (pin "41") (pinfunction "GPIO37_41") (pintype "passive+no_connect"))
    )
    (net (code "57") (name "unconnected-(U2-GPIO38-Pad42)") (class "Default")
      (node (ref "U2") (pin "42") (pinfunction "GPIO38_42") (pintype "passive+no_connect"))
    )
    (net (code "58") (name "unconnected-(U2-GPIO45-Pad50)") (class "Default")
      (node (ref "U2") (pin "50") (pinfunction "GPIO45_50") (pintype "passive+no_connect"))
    )
    (net (code "59") (name "unconnected-(U2-GPIO46-Pad55)") (class "Default")
      (node (ref "U2") (pin "55") (pinfunction "GPIO46_55") (pintype "passive+no_connect"))
    )
    (net (code "60") (name "unconnected-(U2-MTCK-Pad43)") (class "Default")
      (node (ref "U2") (pin "43") (pinfunction "MTCK_43") (pintype "passive+no_connect"))
    )
    (net (code "61") (name "unconnected-(U2-MTD0-Pad44)") (class "Default")
      (node (ref "U2") (pin "44") (pinfunction "MTD0_44") (pintype "passive+no_connect"))
    )
    (net (code "62") (name "unconnected-(U2-MTDI-Pad46)") (class "Default")
      (node (ref "U2") (pin "46") (pinfunction "MTDI_46") (pintype "passive+no_connect"))
    )
    (net (code "63") (name "unconnected-(U2-MTMS-Pad47)") (class "Default")
      (node (ref "U2") (pin "47") (pinfunction "MTMS_47") (pintype "passive+no_connect"))
    )
    (net (code "64") (name "unconnected-(U2-SPICLK-Pad34)") (class "Default")
      (node (ref "U2") (pin "34") (pinfunction "SPICLK_34") (pintype "passive+no_connect"))
    )
    (net (code "65") (name "unconnected-(U2-SPICS0-Pad33)") (class "Default")
      (node (ref "U2") (pin "33") (pinfunction "SPICS0_33") (pintype "passive+no_connect"))
    )
    (net (code "66") (name "unconnected-(U2-SPICS1-Pad29)") (class "Default")
      (node (ref "U2") (pin "29") (pinfunction "SPICS1_29") (pintype "passive+no_connect"))
    )
    (net (code "67") (name "unconnected-(U2-SPID-Pad36)") (class "Default")
      (node (ref "U2") (pin "36") (pinfunction "SPID_36") (pintype "passive+no_connect"))
    )
    (net (code "68") (name "unconnected-(U2-SPIHD-Pad31)") (class "Default")
      (node (ref "U2") (pin "31") (pinfunction "SPIHD_31") (pintype "passive+no_connect"))
    )
    (net (code "69") (name "unconnected-(U2-SPIQ-Pad35)") (class "Default")
      (node (ref "U2") (pin "35") (pinfunction "SPIQ_35") (pintype "passive+no_connect"))
    )
    (net (code "70") (name "unconnected-(U2-SPIWP-Pad32)") (class "Default")
      (node (ref "U2") (pin "32") (pinfunction "SPIWP_32") (pintype "passive+no_connect"))
    )
    (net (code "71") (name "unconnected-(U2-U0RXD-Pad49)") (class "Default")
      (node (ref "U2") (pin "49") (pinfunction "U0RXD_49") (pintype "passive+no_connect"))
    )
    (net (code "72") (name "unconnected-(U2-U0TXD-Pad48)") (class "Default")
      (node (ref "U2") (pin "48") (pinfunction "U0TXD_48") (pintype "passive+no_connect"))
    )
    (net (code "73") (name "unconnected-(U2-XTAL_32K_N-Pad22)") (class "Default")
      (node (ref "U2") (pin "22") (pinfunction "XTAL_32K_N_22") (pintype "passive+no_connect"))
    )
    (net (code "74") (name "unconnected-(U2-XTAL_32K_P-Pad21)") (class "Default")
      (node (ref "U2") (pin "21") (pinfunction "XTAL_32K_P_21") (pintype "passive+no_connect"))
    )
    (net (code "75") (name "unconnected-(U3-NC-Pad4)") (class "Default")
      (node (ref "U3") (pin "4") (pinfunction "NC_4") (pintype "passive+no_connect"))
    )
    (net (code "76") (name "unconnected-(U4-NC-Pad1)") (class "Default")
      (node (ref "U4") (pin "1") (pinfunction "NC_1") (pintype "passive+no_connect"))
    )
  )
)
